# 3v3_power.net
KiCad netlist of a schematic drawn in Altium Designer
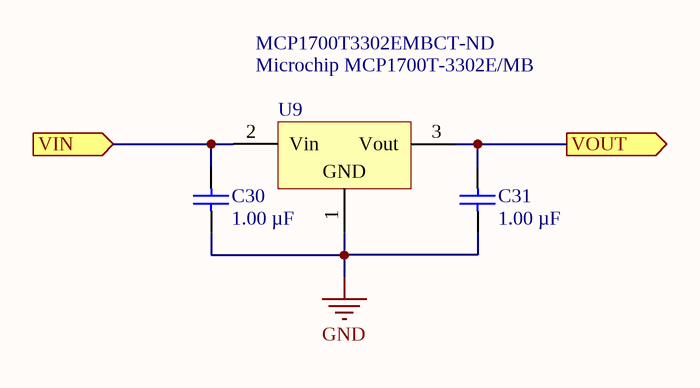
[diagram p0: 3v3_power.SchDoc]

(export (version "E")
  (design (tool "Eeschema 10.0.6"))
  (components
    (comp (ref "C30")
      (value "Würth Elektronik 885012207051")
      (footprint "PCB-xrh88671zmf2jss4mnlt-1")
      (description "Capacitor [Würth Elektronik] 885012207051 Capacitor")
      (fields (field (name "MANUFACTURER PART NUMBER") "885012207051") (field (name "CAPACITANCE") "1.00 µF"))
      (libsource (lib "CommunityVault") (part "CMP-7104bbe86e53aec3-1"))
    )
    (comp (ref "C31")
      (value "Würth Elektronik 885012207051")
      (footprint "PCB-xrh88671zmf2jss4mnlt-1")
      (description "Capacitor [Würth Elektronik] 885012207051 Capacitor")
      (fields (field (name "MANUFACTURER PART NUMBER") "885012207051") (field (name "CAPACITANCE") "1.00 µF"))
      (libsource (lib "CommunityVault") (part "CMP-7104bbe86e53aec3-1"))
    )
    (comp (ref "U9")
      (value "Microchip MCP1700T-3302E/MB")
      (footprint "SOT-89-MB3_L")
      (description "LDO voltage regulator [Microchip] MCP1700T-3302E/MB LDO voltage regulator")
      (libsource (lib "CommunityVault") (part "SYM-54ee9dec78a18b29-1"))
    )
  )
  (nets
    (net (code "1") (name "/VIN") (class "Default")
      (node (ref "C30") (pin "2") (pinfunction "2_2") (pintype "passive"))
      (node (ref "U9") (pin "2") (pinfunction "Vin_2") (pintype "power_in"))
    )
    (net (code "2") (name "/VOUT") (class "Default")
      (node (ref "C31") (pin "2") (pinfunction "2_2") (pintype "passive"))
      (node (ref "U9") (pin "3") (pinfunction "Vout_3") (pintype "power_in"))
    )
    (net (code "3") (name "GND") (class "Default")
      (node (ref "C30") (pin "1") (pinfunction "1_1") (pintype "passive"))
      (node (ref "C31") (pin "1") (pinfunction "1_1") (pintype "passive"))
      (node (ref "U9") (pin "1") (pinfunction "GND_1") (pintype "power_in"))
    )
  )
)
